# 1-Schematic_BlinkingLightBoard.net
KiCad netlist of a schematic drawn in EasyEDA
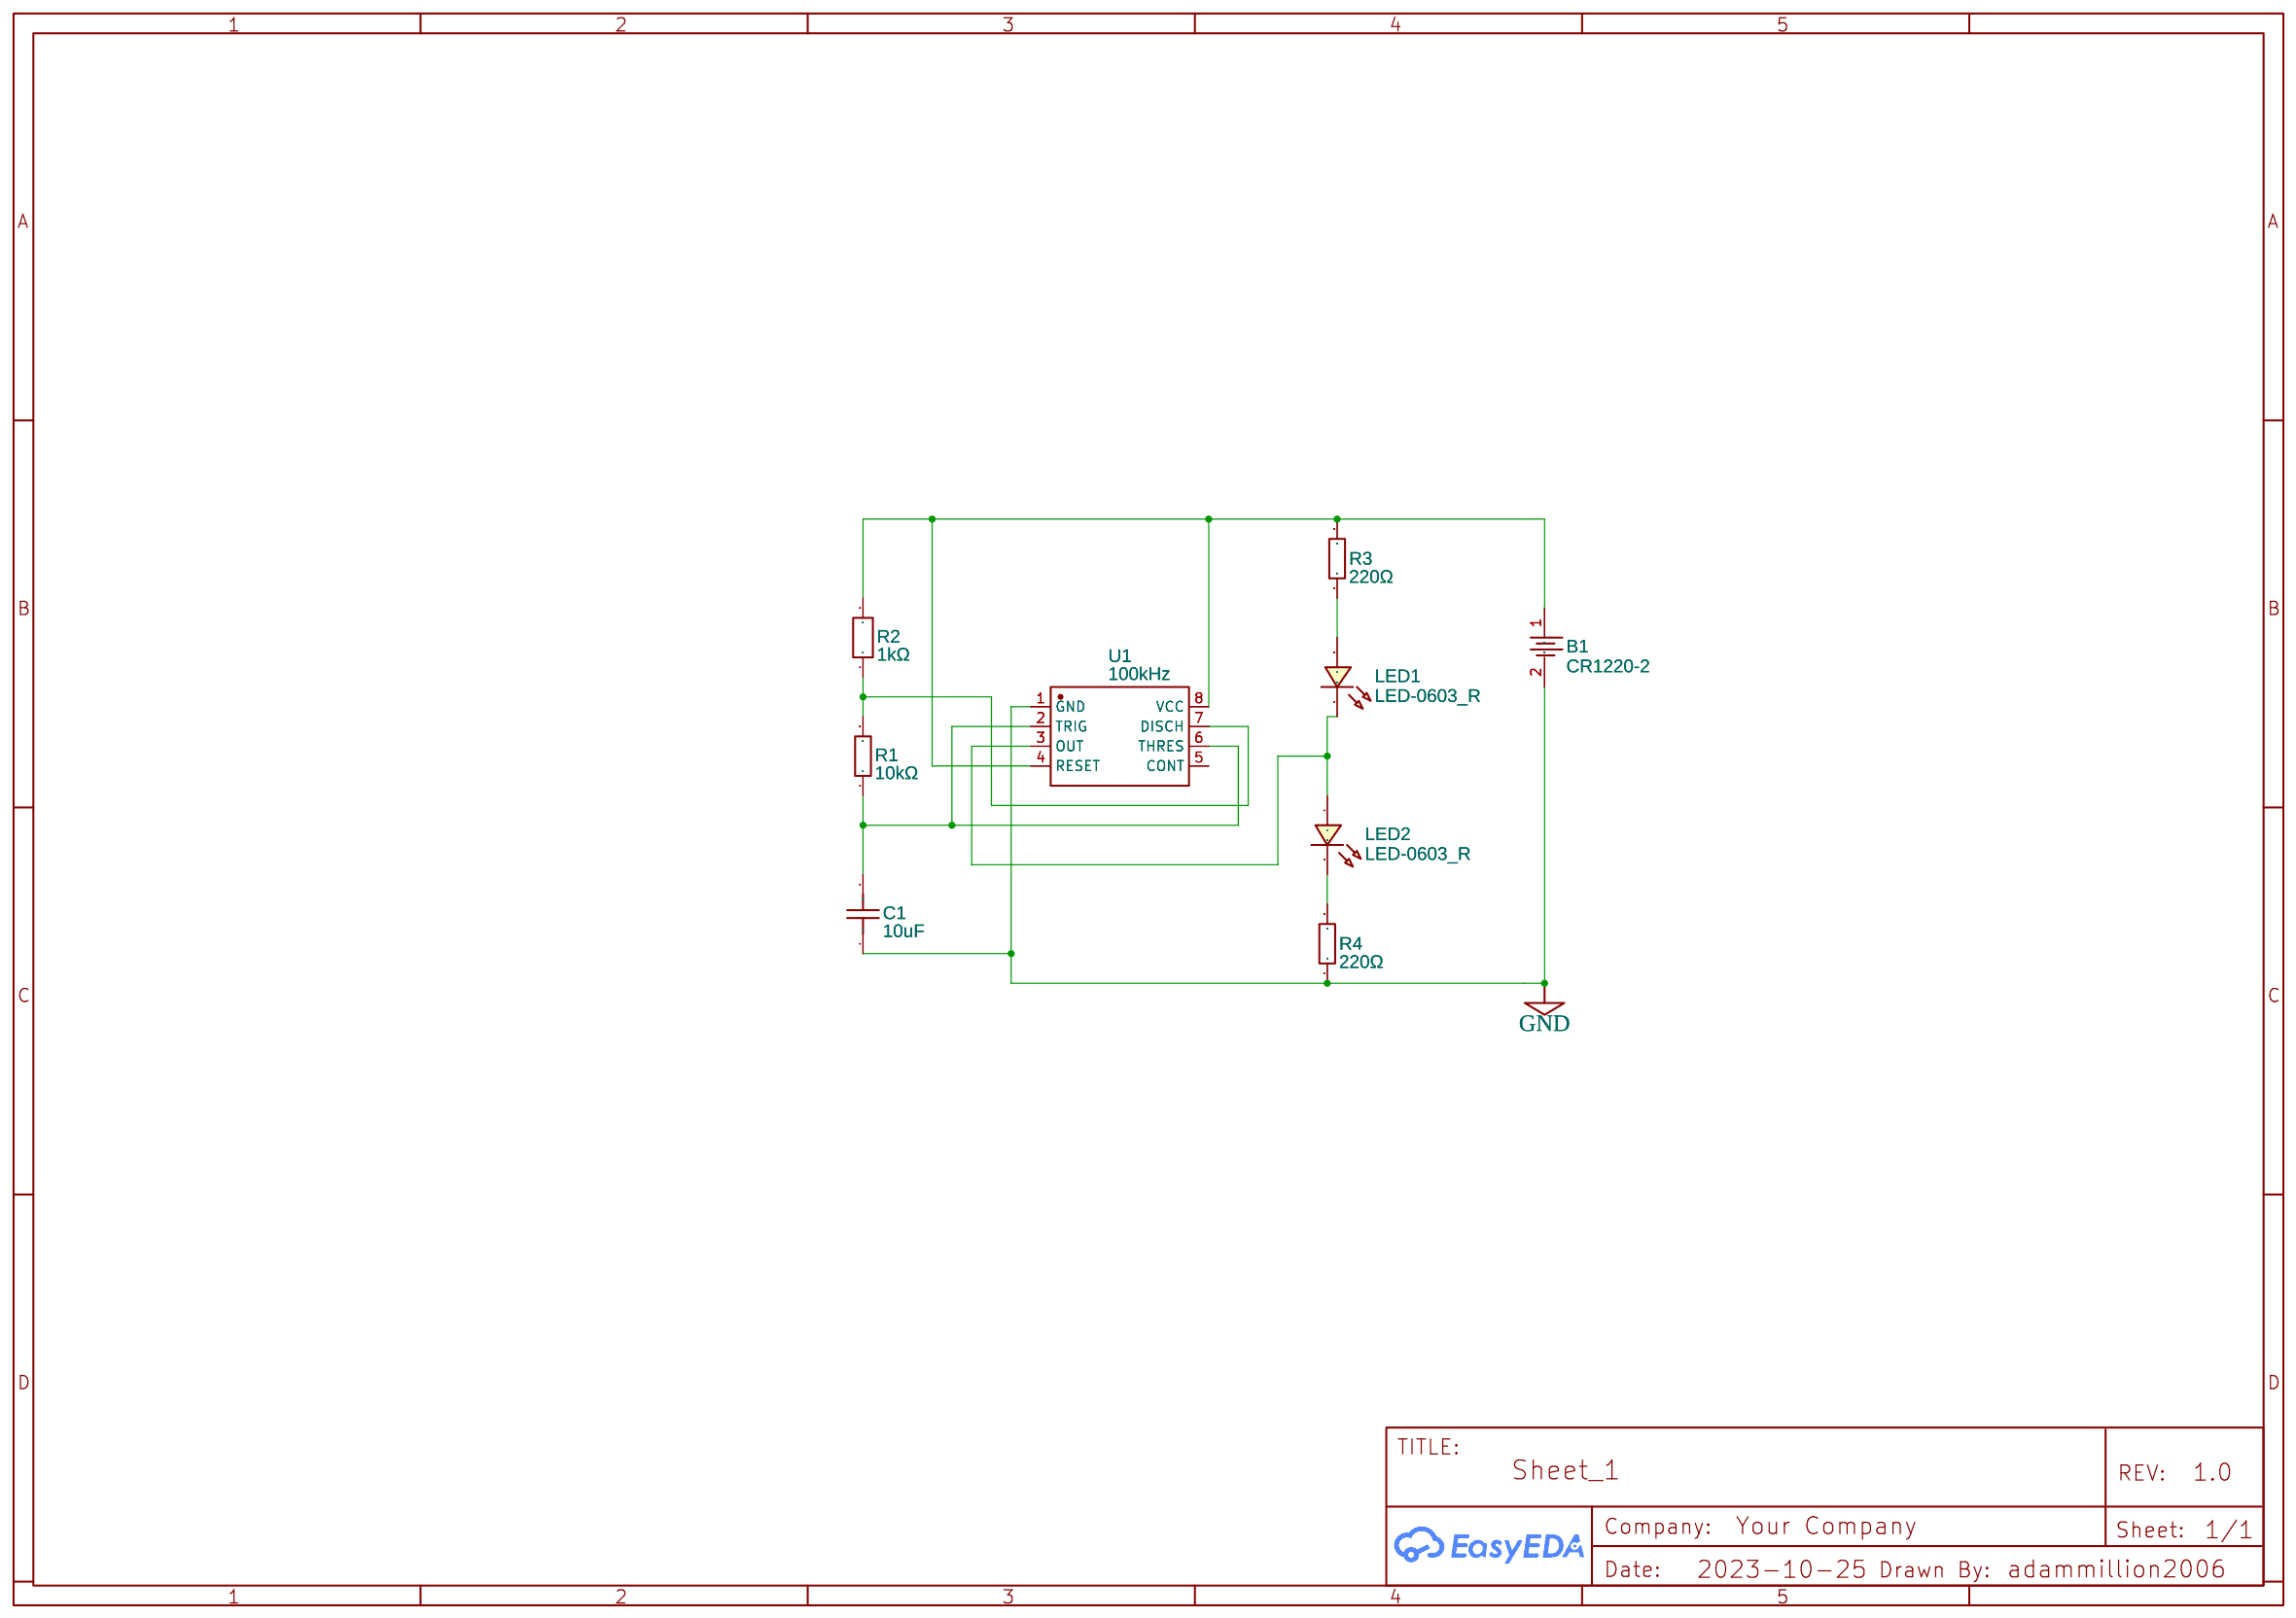
[diagram p0: schematic sheet]

(export (version "E")
  (design (tool "Eeschema 10.0.6"))
  (components
    (comp (ref "B1")
      (value "CR1220-2")
      (fields (field (name "Manufacturer") "Q&J"))
      (libsource (lib "") (part "CR1220-2"))
    )
    (comp (ref "C1")
      (value "10uF")
      (fields
        (field (name "Manufacturer Part") "GRM155R60J106ME05D")
        (field (name "Manufacturer") "muRata(村田)")
      )
      (libsource (lib "") (part "GRM155R60J106ME05D"))
    )
    (comp (ref "LED1")
      (value "LED-0603_R")
      (fields
        (field (name "Manufacturer Part") "19-217/R6C-AL1M2VY/3T")
        (field (name "Manufacturer") "EVERLIGHT(台湾亿光)")
      )
      (libsource (lib "") (part "LED-0603_R"))
    )
    (comp (ref "LED2")
      (value "LED-0603_R")
      (fields
        (field (name "Manufacturer Part") "19-217/R6C-AL1M2VY/3T")
        (field (name "Manufacturer") "EVERLIGHT(台湾亿光)")
      )
      (libsource (lib "") (part "LED-0603_R"))
    )
    (comp (ref "R1")
      (value "10kΩ")
      (fields (field (name "Manufacturer Part") "MFR-12FTE52-10K") (field (name "Manufacturer") "YAGEO(国巨)"))
      (libsource (lib "") (part "MFR-12FTE52-10K"))
    )
    (comp (ref "R2")
      (value "1kΩ")
      (fields (field (name "Manufacturer Part") "MF0207FTE52-1K") (field (name "Manufacturer") "YAGEO(国巨)"))
      (libsource (lib "") (part "MF0207FTE52-1K"))
    )
    (comp (ref "R3")
      (value "220Ω")
      (fields (field (name "Manufacturer Part") "EWWR0006J220RT9") (field (name "Manufacturer") "RESI(开步睿思）"))
      (libsource (lib "") (part "EWWR0006J220RT9"))
    )
    (comp (ref "R4")
      (value "220Ω")
      (fields (field (name "Manufacturer Part") "EWWR0006J220RT9") (field (name "Manufacturer") "RESI(开步睿思）"))
      (libsource (lib "") (part "EWWR0006J220RT9"))
    )
    (comp (ref "U1")
      (value "100kHz")
      (fields (field (name "Manufacturer Part") "NE555P") (field (name "Manufacturer") "TI(德州仪器)"))
      (libsource (lib "") (part "NE555P"))
    )
  )
  (nets
    (net (code "1") (name "GND") (class "Default")
      (node (ref "B1") (pin "2") (pinfunction "2_2") (pintype "input"))
      (node (ref "C1") (pin "1") (pinfunction "1_1") (pintype "unspecified"))
      (node (ref "R4") (pin "1") (pinfunction "1_1") (pintype "unspecified"))
      (node (ref "U1") (pin "1") (pinfunction "GND_1") (pintype "unspecified"))
    )
    (net (code "2") (name "Net-(LED1-Pad1)") (class "Default")
      (node (ref "LED1") (pin "1") (pinfunction "1_1") (pintype "unspecified"))
      (node (ref "R3") (pin "1") (pinfunction "1_1") (pintype "unspecified"))
    )
    (net (code "3") (name "Net-(LED2-Pad2)") (class "Default")
      (node (ref "LED2") (pin "2") (pinfunction "2_2") (pintype "unspecified"))
      (node (ref "R4") (pin "2") (pinfunction "2_2") (pintype "unspecified"))
    )
    (net (code "4") (name "Net-(U1-DISCH)") (class "Default")
      (node (ref "R1") (pin "2") (pinfunction "2_2") (pintype "unspecified"))
      (node (ref "R2") (pin "1") (pinfunction "1_1") (pintype "unspecified"))
      (node (ref "U1") (pin "7") (pinfunction "DISCH_7") (pintype "unspecified"))
    )
    (net (code "5") (name "Net-(U1-OUT)") (class "Default")
      (node (ref "LED1") (pin "2") (pinfunction "2_2") (pintype "unspecified"))
      (node (ref "LED2") (pin "1") (pinfunction "1_1") (pintype "unspecified"))
      (node (ref "U1") (pin "3") (pinfunction "OUT_3") (pintype "unspecified"))
    )
    (net (code "6") (name "Net-(U1-RESET)") (class "Default")
      (node (ref "B1") (pin "1") (pinfunction "1_1") (pintype "input"))
      (node (ref "R2") (pin "2") (pinfunction "2_2") (pintype "unspecified"))
      (node (ref "R3") (pin "2") (pinfunction "2_2") (pintype "unspecified"))
      (node (ref "U1") (pin "4") (pinfunction "RESET_4") (pintype "unspecified"))
      (node (ref "U1") (pin "8") (pinfunction "VCC_8") (pintype "unspecified"))
    )
    (net (code "7") (name "Net-(U1-THRES)") (class "Default")
      (node (ref "C1") (pin "2") (pinfunction "2_2") (pintype "unspecified"))
      (node (ref "R1") (pin "1") (pinfunction "1_1") (pintype "unspecified"))
      (node (ref "U1") (pin "2") (pinfunction "TRIG_2") (pintype "unspecified"))
      (node (ref "U1") (pin "6") (pinfunction "THRES_6") (pintype "unspecified"))
    )
    (net (code "8") (name "unconnected-(U1-CONT-Pad5)") (class "Default")
      (node (ref "U1") (pin "5") (pinfunction "CONT_5") (pintype "unspecified"))
    )
  )
)
